# ft240x.net
KiCad netlist of a schematic drawn in EAGLE
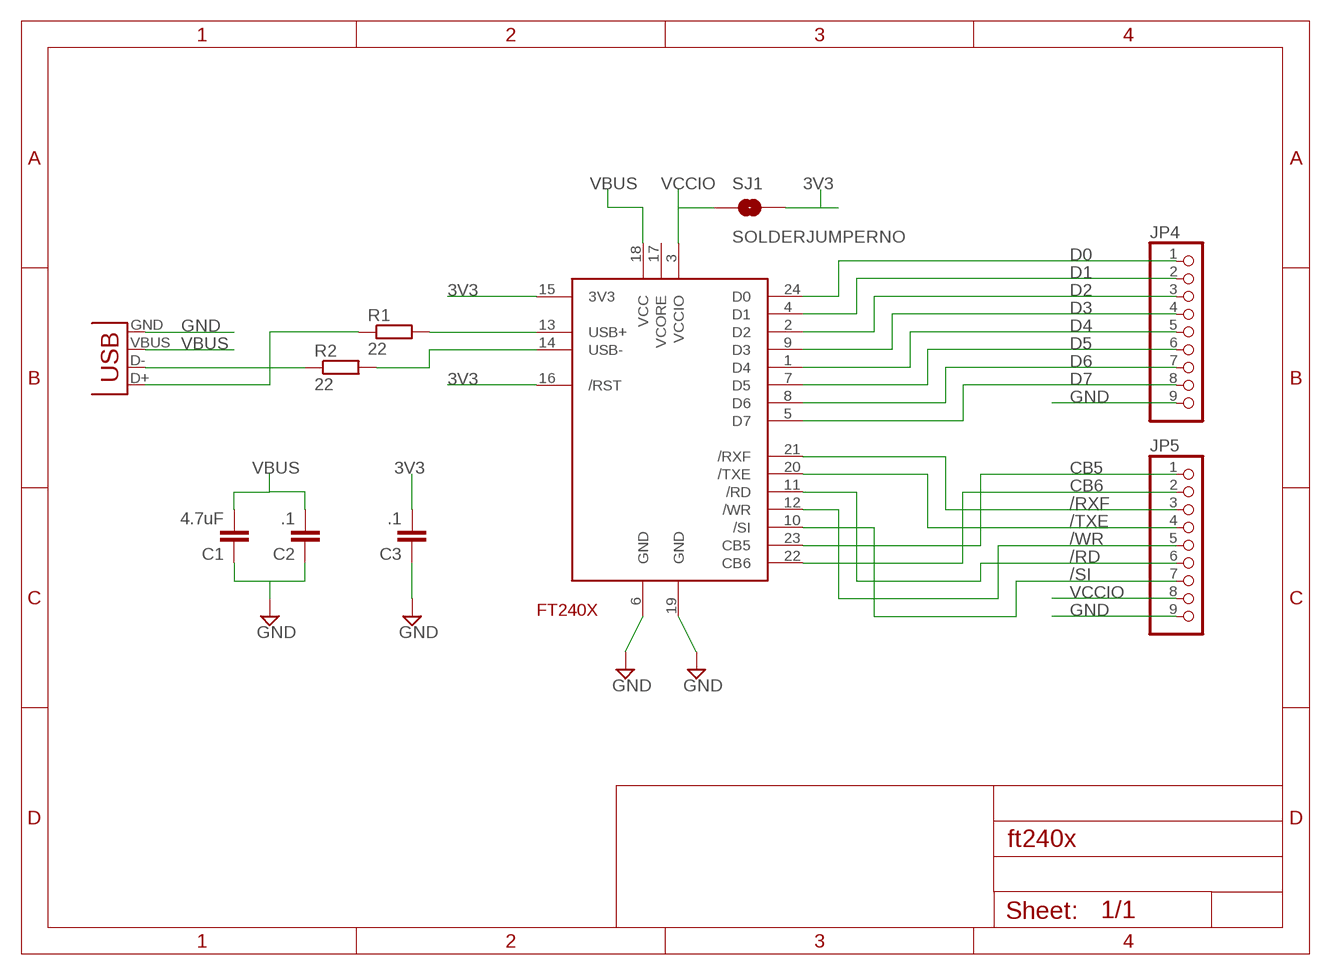
[diagram p0: schematic, sheet 1]

(export (version "E")
  (design (tool "Eeschema 10.0.6"))
  (components
    (comp (ref "C1")
      (value "4.7uF")
      (footprint "eagle-import:C0603")
      (libsource (lib "eagle-import") (part "C-EUC0603"))
    )
    (comp (ref "C2")
      (value ".1")
      (footprint "eagle-import:C0603")
      (libsource (lib "eagle-import") (part "C-EUC0603"))
    )
    (comp (ref "C3")
      (value ".1")
      (footprint "eagle-import:C0603")
      (libsource (lib "eagle-import") (part "C-EUC0603"))
    )
    (comp (ref "JP3")
      (value "USBSMD")
      (footprint "eagle-import:USB-MINIB")
      (libsource (lib "eagle-import") (part "USBSMD"))
    )
    (comp (ref "JP4")
      (value "HEADER-1X970MIL")
      (footprint "eagle-import:1X09_ROUND_70")
      (libsource (lib "eagle-import") (part "HEADER-1X970MIL"))
    )
    (comp (ref "JP5")
      (value "HEADER-1X970MIL")
      (footprint "eagle-import:1X09_ROUND_70")
      (libsource (lib "eagle-import") (part "HEADER-1X970MIL"))
    )
    (comp (ref "R1")
      (value "22")
      (footprint "eagle-import:R0603")
      (libsource (lib "eagle-import") (part "R-EU_R0603"))
    )
    (comp (ref "R2")
      (value "22")
      (footprint "eagle-import:R0603")
      (libsource (lib "eagle-import") (part "R-EU_R0603"))
    )
    (comp (ref "SJ1")
      (value "SOLDERJUMPERNO")
      (footprint "eagle-import:SJ_2S-NO")
      (libsource (lib "eagle-import") (part "SOLDERJUMPERNO"))
    )
    (comp (ref "U$1")
      (value "IHSAN_FT240X")
      (footprint "eagle-import:SSOP24")
      (libsource (lib "eagle-import") (part "IHSAN_FT240X"))
    )
  )
  (nets
    (net (code "1") (name "/3V3") (class "Default")
      (node (ref "C3") (pin "2") (pinfunction "2_2") (pintype "passive"))
      (node (ref "SJ1") (pin "2") (pinfunction "2_2") (pintype "passive"))
      (node (ref "U$1") (pin "15") (pinfunction "3V3_15") (pintype "bidirectional"))
      (node (ref "U$1") (pin "16") (pinfunction "/RST_16") (pintype "bidirectional"))
    )
    (net (code "2") (name "/CB5") (class "Default")
      (node (ref "JP5") (pin "1") (pinfunction "1_1") (pintype "passive"))
      (node (ref "U$1") (pin "23") (pinfunction "CB5_23") (pintype "bidirectional"))
    )
    (net (code "3") (name "/CB6") (class "Default")
      (node (ref "JP5") (pin "2") (pinfunction "2_2") (pintype "passive"))
      (node (ref "U$1") (pin "22") (pinfunction "CB6_22") (pintype "bidirectional"))
    )
    (net (code "4") (name "/D0") (class "Default")
      (node (ref "JP4") (pin "1") (pinfunction "1_1") (pintype "passive"))
      (node (ref "U$1") (pin "24") (pinfunction "D0_24") (pintype "bidirectional"))
    )
    (net (code "5") (name "/D1") (class "Default")
      (node (ref "JP4") (pin "2") (pinfunction "2_2") (pintype "passive"))
      (node (ref "U$1") (pin "4") (pinfunction "D1_4") (pintype "bidirectional"))
    )
    (net (code "6") (name "/D2") (class "Default")
      (node (ref "JP4") (pin "3") (pinfunction "3_3") (pintype "passive"))
      (node (ref "U$1") (pin "2") (pinfunction "D2_2") (pintype "bidirectional"))
    )
    (net (code "7") (name "/D3") (class "Default")
      (node (ref "JP4") (pin "4") (pinfunction "4_4") (pintype "passive"))
      (node (ref "U$1") (pin "9") (pinfunction "D3_9") (pintype "bidirectional"))
    )
    (net (code "8") (name "/D4") (class "Default")
      (node (ref "JP4") (pin "5") (pinfunction "5_5") (pintype "passive"))
      (node (ref "U$1") (pin "1") (pinfunction "D4_1") (pintype "bidirectional"))
    )
    (net (code "9") (name "/D5") (class "Default")
      (node (ref "JP4") (pin "6") (pinfunction "6_6") (pintype "passive"))
      (node (ref "U$1") (pin "7") (pinfunction "D5_7") (pintype "bidirectional"))
    )
    (net (code "10") (name "/D6") (class "Default")
      (node (ref "JP4") (pin "7") (pinfunction "7_7") (pintype "passive"))
      (node (ref "U$1") (pin "8") (pinfunction "D6_8") (pintype "bidirectional"))
    )
    (net (code "11") (name "/D7") (class "Default")
      (node (ref "JP4") (pin "8") (pinfunction "8_8") (pintype "passive"))
      (node (ref "U$1") (pin "5") (pinfunction "D7_5") (pintype "bidirectional"))
    )
    (net (code "12") (name "/VBUS") (class "Default")
      (node (ref "C1") (pin "2") (pinfunction "2_2") (pintype "passive"))
      (node (ref "C2") (pin "2") (pinfunction "2_2") (pintype "passive"))
      (node (ref "JP3") (pin "VBUS") (pinfunction "VBUS_VBUS") (pintype "bidirectional"))
      (node (ref "U$1") (pin "18") (pinfunction "VCC_18") (pintype "bidirectional"))
    )
    (net (code "13") (name "/VCCIO") (class "Default")
      (node (ref "JP5") (pin "8") (pinfunction "8_8") (pintype "passive"))
      (node (ref "SJ1") (pin "1") (pinfunction "1_1") (pintype "passive"))
      (node (ref "U$1") (pin "3") (pinfunction "VCCIO_3") (pintype "bidirectional"))
    )
    (net (code "14") (name "/{slash}RD") (class "Default")
      (node (ref "JP5") (pin "6") (pinfunction "6_6") (pintype "passive"))
      (node (ref "U$1") (pin "11") (pinfunction "/RD_11") (pintype "bidirectional"))
    )
    (net (code "15") (name "/{slash}RXF") (class "Default")
      (node (ref "JP5") (pin "3") (pinfunction "3_3") (pintype "passive"))
      (node (ref "U$1") (pin "21") (pinfunction "/RXF_21") (pintype "bidirectional"))
    )
    (net (code "16") (name "/{slash}SI") (class "Default")
      (node (ref "JP5") (pin "7") (pinfunction "7_7") (pintype "passive"))
      (node (ref "U$1") (pin "10") (pinfunction "/SI_10") (pintype "bidirectional"))
    )
    (net (code "17") (name "/{slash}TXE") (class "Default")
      (node (ref "JP5") (pin "4") (pinfunction "4_4") (pintype "passive"))
      (node (ref "U$1") (pin "20") (pinfunction "/TXE_20") (pintype "bidirectional"))
    )
    (net (code "18") (name "/{slash}WR") (class "Default")
      (node (ref "JP5") (pin "5") (pinfunction "5_5") (pintype "passive"))
      (node (ref "U$1") (pin "12") (pinfunction "/WR_12") (pintype "bidirectional"))
    )
    (net (code "19") (name "GND") (class "Default")
      (node (ref "C1") (pin "1") (pinfunction "1_1") (pintype "passive"))
      (node (ref "C2") (pin "1") (pinfunction "1_1") (pintype "passive"))
      (node (ref "C3") (pin "1") (pinfunction "1_1") (pintype "passive"))
      (node (ref "JP3") (pin "GND") (pinfunction "GND_GND") (pintype "bidirectional"))
      (node (ref "JP4") (pin "9") (pinfunction "9_9") (pintype "passive"))
      (node (ref "JP5") (pin "9") (pinfunction "9_9") (pintype "passive"))
      (node (ref "U$1") (pin "19") (pinfunction "GND_19") (pintype "bidirectional"))
      (node (ref "U$1") (pin "6") (pinfunction "GND_6") (pintype "bidirectional"))
    )
    (net (code "20") (name "Net-(JP3-PadD+)") (class "Default")
      (node (ref "JP3") (pin "D+") (pinfunction "D+_D+") (pintype "bidirectional"))
      (node (ref "R1") (pin "1") (pinfunction "1_1") (pintype "passive"))
    )
    (net (code "21") (name "Net-(JP3-PadD-)") (class "Default")
      (node (ref "JP3") (pin "D-") (pinfunction "D-_D-") (pintype "bidirectional"))
      (node (ref "R2") (pin "1") (pinfunction "1_1") (pintype "passive"))
    )
    (net (code "22") (name "Net-(U$1-USB+)") (class "Default")
      (node (ref "R1") (pin "2") (pinfunction "2_2") (pintype "passive"))
      (node (ref "U$1") (pin "13") (pinfunction "USB+_13") (pintype "bidirectional"))
    )
    (net (code "23") (name "Net-(U$1-USB-)") (class "Default")
      (node (ref "R2") (pin "2") (pinfunction "2_2") (pintype "passive"))
      (node (ref "U$1") (pin "14") (pinfunction "USB-_14") (pintype "bidirectional"))
    )
    (net (code "24") (name "unconnected-(U$1-VCORE-Pad17)") (class "Default")
      (node (ref "U$1") (pin "17") (pinfunction "VCORE_17") (pintype "bidirectional"))
    )
  )
)
